# MCP2518_PINOUT.net
KiCad netlist of a schematic drawn in Altium Designer
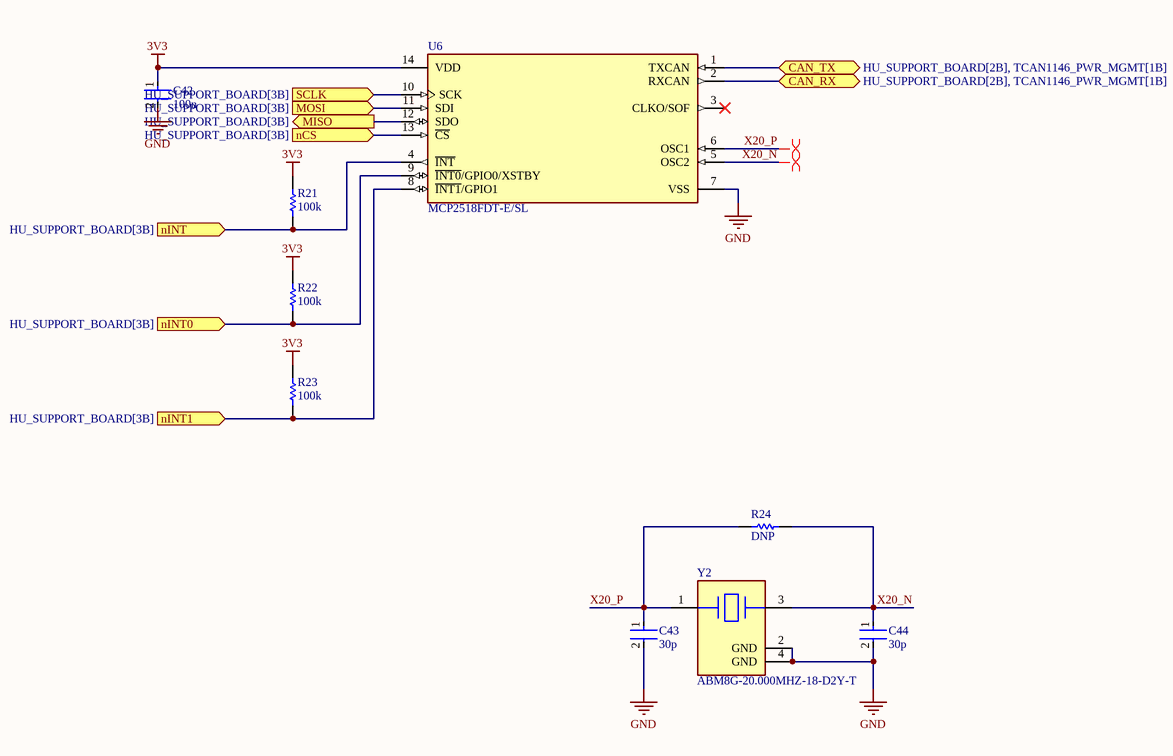
[diagram p0: MCP2518_PINOUT.SchDoc]

(export (version "E")
  (design (tool "Eeschema 10.0.6"))
  (components
    (comp (ref "C42")
      (value "100n")
      (footprint "FP-0402-L_1_0_0_05-W_0_5-IPC_A")
      (description "LARGE PADS, 0402 CAP, CHANGE COMMENT TO MATCH REAL P/N")
      (libsource (lib "Space Concordia") (part "b4654b650e69147ec39a6b967a45e02"))
    )
    (comp (ref "C43")
      (value "30p")
      (footprint "FP-0402-L_1_0_0_05-W_0_5-IPC_A")
      (description "LARGE PADS, 0402 CAP, CHANGE COMMENT TO MATCH REAL P/N")
      (libsource (lib "Space Concordia") (part "b4654b650e69147ec39a6b967a45e02"))
    )
    (comp (ref "C44")
      (value "30p")
      (footprint "FP-0402-L_1_0_0_05-W_0_5-IPC_A")
      (description "LARGE PADS, 0402 CAP, CHANGE COMMENT TO MATCH REAL P/N")
      (libsource (lib "Space Concordia") (part "b4654b650e69147ec39a6b967a45e02"))
    )
    (comp (ref "R21")
      (value "100k")
      (footprint "R0603B")
      (description "Resistor")
      (libsource (lib "Space Concordia") (part "Resistor"))
    )
    (comp (ref "R22")
      (value "100k")
      (footprint "R0603B")
      (description "Resistor")
      (libsource (lib "Space Concordia") (part "Resistor"))
    )
    (comp (ref "R23")
      (value "100k")
      (footprint "R0603B")
      (description "Resistor")
      (libsource (lib "Space Concordia") (part "Resistor"))
    )
    (comp (ref "R24")
      (value "DNP")
      (footprint "R0603B")
      (description "Resistor")
      (libsource (lib "Space Concordia") (part "Resistor"))
    )
    (comp (ref "U6")
      (value "MCP2518FDT-E/SL")
      (footprint "FP-C04-065-SL-IPC_C")
      (description "IC CAN CONTROLLER SPI 14SOIC")
      (libsource (lib "Altium Content Vault") (part "48378335c028dfc4faaf2298fb5e2a1"))
    )
    (comp (ref "Y2")
      (value "ABM8G-20.000MHZ-18-D2Y-T")
      (footprint "FP-ABM8G-MFG")
      (description "Crystal 20MHz ±20ppm (Tol) ±30ppm (Stability) 18pF FUND 80Ω 4-Pin SMD T/R")
      (fields (field (name "TOLERANCE") "20ppm"))
      (libsource (lib "Altium Content Vault") (part "48e526d86b7f2615d98721063c72f49"))
    )
  )
  (nets
    (net (code "1") (name "/CAN_RX") (class "Default")
      (node (ref "U6") (pin "2") (pinfunction "RXCAN_2") (pintype "output"))
    )
    (net (code "2") (name "/CAN_TX") (class "Default")
      (node (ref "U6") (pin "1") (pinfunction "TXCAN_1") (pintype "input"))
    )
    (net (code "3") (name "/MISO") (class "Default")
      (node (ref "U6") (pin "12") (pinfunction "SDO_12") (pintype "bidirectional"))
    )
    (net (code "4") (name "/MOSI") (class "Default")
      (node (ref "U6") (pin "11") (pinfunction "SDI_11") (pintype "input"))
    )
    (net (code "5") (name "/SCLK") (class "Default")
      (node (ref "U6") (pin "10") (pinfunction "SCK_10") (pintype "input"))
    )
    (net (code "6") (name "/X20_N") (class "Default")
      (node (ref "C44") (pin "1") (pinfunction "1_1") (pintype "passive"))
      (node (ref "R24") (pin "2") (pinfunction "2_2") (pintype "passive"))
      (node (ref "U6") (pin "5") (pinfunction "OSC2_5") (pintype "input"))
      (node (ref "Y2") (pin "3") (pinfunction "3_3") (pintype "passive"))
    )
    (net (code "7") (name "/X20_P") (class "Default")
      (node (ref "C43") (pin "1") (pinfunction "1_1") (pintype "passive"))
      (node (ref "R24") (pin "1") (pinfunction "1_1") (pintype "passive"))
      (node (ref "U6") (pin "6") (pinfunction "OSC1_6") (pintype "input"))
      (node (ref "Y2") (pin "1") (pinfunction "1_1") (pintype "passive"))
    )
    (net (code "8") (name "/nCS") (class "Default")
      (node (ref "U6") (pin "13") (pinfunction "~{CS}_13") (pintype "input"))
    )
    (net (code "9") (name "/nINT") (class "Default")
      (node (ref "R21") (pin "2") (pinfunction "2_2") (pintype "passive"))
      (node (ref "U6") (pin "4") (pinfunction "~{INT}_4") (pintype "output"))
    )
    (net (code "10") (name "/nINT0") (class "Default")
      (node (ref "R22") (pin "2") (pinfunction "2_2") (pintype "passive"))
      (node (ref "U6") (pin "9") (pinfunction "~{INT0}/GPIO0/XSTBY_9") (pintype "bidirectional"))
    )
    (net (code "11") (name "/nINT1") (class "Default")
      (node (ref "R23") (pin "2") (pinfunction "2_2") (pintype "passive"))
      (node (ref "U6") (pin "8") (pinfunction "~{INT1}/GPIO1_8") (pintype "bidirectional"))
    )
    (net (code "12") (name "3V3") (class "Default")
      (node (ref "C42") (pin "1") (pinfunction "1_1") (pintype "passive"))
      (node (ref "R21") (pin "1") (pinfunction "1_1") (pintype "passive"))
      (node (ref "R22") (pin "1") (pinfunction "1_1") (pintype "passive"))
      (node (ref "R23") (pin "1") (pinfunction "1_1") (pintype "passive"))
      (node (ref "U6") (pin "14") (pinfunction "VDD_14") (pintype "power_in"))
    )
    (net (code "13") (name "GND") (class "Default")
      (node (ref "C42") (pin "2") (pinfunction "2_2") (pintype "passive"))
      (node (ref "C43") (pin "2") (pinfunction "2_2") (pintype "passive"))
      (node (ref "C44") (pin "2") (pinfunction "2_2") (pintype "passive"))
      (node (ref "U6") (pin "7") (pinfunction "VSS_7") (pintype "power_in"))
      (node (ref "Y2") (pin "2") (pinfunction "GND_2") (pintype "power_in"))
      (node (ref "Y2") (pin "4") (pinfunction "GND_4") (pintype "power_in"))
    )
    (net (code "14") (name "unconnected-(U6-CLKO{slash}SOF-Pad3)") (class "Default")
      (node (ref "U6") (pin "3") (pinfunction "CLKO/SOF_3") (pintype "output+no_connect"))
    )
  )
)
